# aHam_just_captm.net
KiCad netlist of a schematic drawn in EAGLE
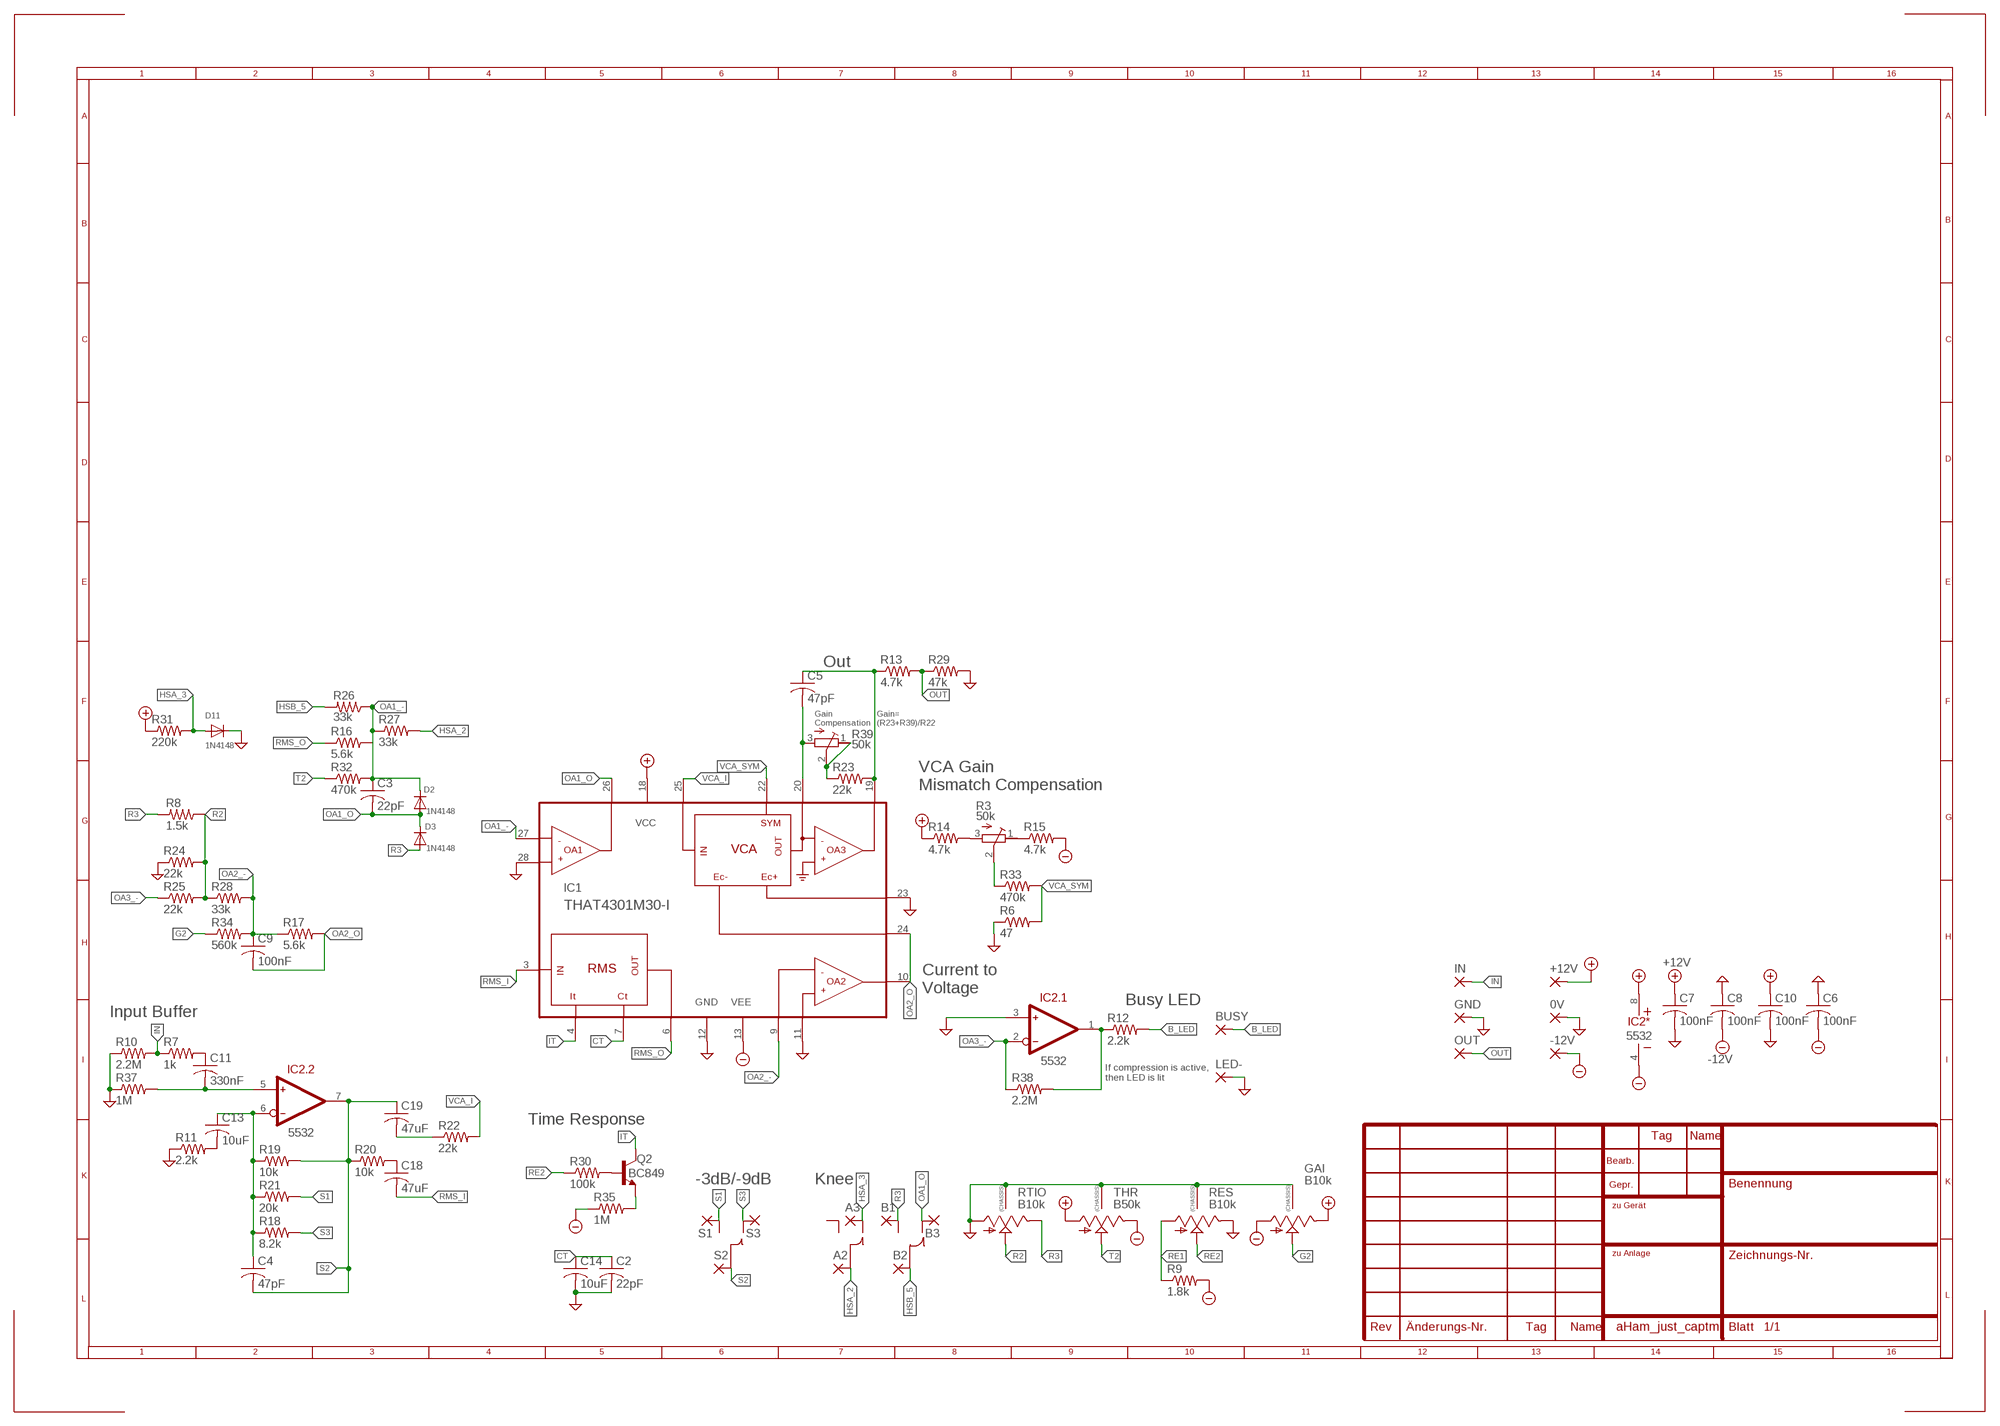
[diagram p0: schematic, sheet 1]

(export (version "E")
  (design (tool "Eeschema 10.0.6"))
  (components
    (comp (ref "+12V")
      (value "1,6/0,8")
      (footprint "eagle-import:1,6_0,8")
      (libsource (lib "eagle-import") (part "1,6/0,8"))
    )
    (comp (ref "-12V")
      (value "1,6/0,8")
      (footprint "eagle-import:1,6_0,8")
      (libsource (lib "eagle-import") (part "1,6/0,8"))
    )
    (comp (ref "0V")
      (value "1,6/0,8")
      (footprint "eagle-import:1,6_0,8")
      (libsource (lib "eagle-import") (part "1,6/0,8"))
    )
    (comp (ref "A2")
      (value "1,6/0,8")
      (footprint "eagle-import:1,6_0,8")
      (libsource (lib "eagle-import") (part "1,6/0,8"))
    )
    (comp (ref "A3")
      (value "1,6/0,8")
      (footprint "eagle-import:1,6_0,8")
      (libsource (lib "eagle-import") (part "1,6/0,8"))
    )
    (comp (ref "B1")
      (value "1,6/0,8")
      (footprint "eagle-import:1,6_0,8")
      (libsource (lib "eagle-import") (part "1,6/0,8"))
    )
    (comp (ref "B2")
      (value "1,6/0,8")
      (footprint "eagle-import:1,6_0,8")
      (libsource (lib "eagle-import") (part "1,6/0,8"))
    )
    (comp (ref "B3")
      (value "1,6/0,8")
      (footprint "eagle-import:1,6_0,8")
      (libsource (lib "eagle-import") (part "1,6/0,8"))
    )
    (comp (ref "BUSY")
      (value "1,6/0,8")
      (footprint "eagle-import:1,6_0,8")
      (libsource (lib "eagle-import") (part "1,6/0,8"))
    )
    (comp (ref "C2")
      (value "22pF")
      (footprint "eagle-import:C0805")
      (libsource (lib "eagle-import") (part "C-USC0805"))
    )
    (comp (ref "C3")
      (value "22pF")
      (footprint "eagle-import:C0805")
      (libsource (lib "eagle-import") (part "C-USC0805"))
    )
    (comp (ref "C4")
      (value "47pF")
      (footprint "eagle-import:C0805")
      (libsource (lib "eagle-import") (part "C-USC0805"))
    )
    (comp (ref "C5")
      (value "47pF")
      (footprint "eagle-import:C0805")
      (libsource (lib "eagle-import") (part "C-USC0805"))
    )
    (comp (ref "C6")
      (value "100nF")
      (footprint "eagle-import:C0805")
      (libsource (lib "eagle-import") (part "C-USC0805"))
    )
    (comp (ref "C7")
      (value "100nF")
      (footprint "eagle-import:C0805")
      (libsource (lib "eagle-import") (part "C-USC0805"))
    )
    (comp (ref "C8")
      (value "100nF")
      (footprint "eagle-import:C0805")
      (libsource (lib "eagle-import") (part "C-USC0805"))
    )
    (comp (ref "C9")
      (value "100nF")
      (footprint "eagle-import:C0805")
      (libsource (lib "eagle-import") (part "C-USC0805"))
    )
    (comp (ref "C10")
      (value "100nF")
      (footprint "eagle-import:C0805")
      (libsource (lib "eagle-import") (part "C-USC0805"))
    )
    (comp (ref "C11")
      (value "330nF")
      (footprint "eagle-import:C0805")
      (libsource (lib "eagle-import") (part "C-USC0805"))
    )
    (comp (ref "C13")
      (value "10uF")
      (footprint "eagle-import:C1206")
      (libsource (lib "eagle-import") (part "C-USC1206"))
    )
    (comp (ref "C14")
      (value "10uF")
      (footprint "eagle-import:C1206")
      (libsource (lib "eagle-import") (part "C-USC1206"))
    )
    (comp (ref "C18")
      (value "47uF")
      (footprint "eagle-import:C1206")
      (libsource (lib "eagle-import") (part "C-USC1206"))
    )
    (comp (ref "C19")
      (value "47uF")
      (footprint "eagle-import:C1206")
      (libsource (lib "eagle-import") (part "C-USC1206"))
    )
    (comp (ref "D2")
      (value "1N4148")
      (footprint "eagle-import:SOD-123")
      (libsource (lib "eagle-import") (part "DIODESOD-123"))
    )
    (comp (ref "D3")
      (value "1N4148")
      (footprint "eagle-import:SOD-123")
      (libsource (lib "eagle-import") (part "DIODESOD-123"))
    )
    (comp (ref "D11")
      (value "1N4148")
      (footprint "eagle-import:SOD-123")
      (libsource (lib "eagle-import") (part "DIODESOD-123"))
    )
    (comp (ref "GAI")
      (value "B10k")
      (footprint "eagle-import:9MM_SNAP-IN_POT")
      (libsource (lib "eagle-import") (part "9MM_SNAP-IN_POT_CHASSIS"))
    )
    (comp (ref "GND")
      (value "1,6/0,8")
      (footprint "eagle-import:1,6_0,8")
      (libsource (lib "eagle-import") (part "1,6/0,8"))
    )
    (comp (ref "IC1")
      (value "THAT4301M30-I")
      (footprint "eagle-import:SO30W")
      (libsource (lib "eagle-import") (part "THAT4301M30-I"))
    )
    (comp (ref "IC2")
      (value "5532")
      (footprint "eagle-import:SO-8")
      (libsource (lib "eagle-import") (part "NJM5532M"))
    )
    (comp (ref "IN")
      (value "1,6/0,8")
      (footprint "eagle-import:1,6_0,8")
      (libsource (lib "eagle-import") (part "1,6/0,8"))
    )
    (comp (ref "LED-")
      (value "1,6/0,8")
      (footprint "eagle-import:1,6_0,8")
      (libsource (lib "eagle-import") (part "1,6/0,8"))
    )
    (comp (ref "OUT")
      (value "1,6/0,8")
      (footprint "eagle-import:1,6_0,8")
      (libsource (lib "eagle-import") (part "1,6/0,8"))
    )
    (comp (ref "Q2")
      (value "BC849")
      (footprint "eagle-import:SOT23-BEC")
      (libsource (lib "eagle-import") (part "-NPN-SOT23-BECBC849"))
    )
    (comp (ref "R3")
      (value "50k")
      (footprint "eagle-import:RTRIM3314G")
      (libsource (lib "eagle-import") (part "R-TRIMM3314G"))
    )
    (comp (ref "R6")
      (value "47")
      (footprint "eagle-import:R0805")
      (libsource (lib "eagle-import") (part "R-US_R0805"))
    )
    (comp (ref "R7")
      (value "1k")
      (footprint "eagle-import:R0805")
      (libsource (lib "eagle-import") (part "R-US_R0805"))
    )
    (comp (ref "R8")
      (value "1.5k")
      (footprint "eagle-import:R0805")
      (libsource (lib "eagle-import") (part "R-US_R0805"))
    )
    (comp (ref "R9")
      (value "1.8k")
      (footprint "eagle-import:R0805")
      (libsource (lib "eagle-import") (part "R-US_R0805"))
    )
    (comp (ref "R10")
      (value "2.2M")
      (footprint "eagle-import:R0805")
      (libsource (lib "eagle-import") (part "R-US_R0805"))
    )
    (comp (ref "R11")
      (value "2.2k")
      (footprint "eagle-import:R0805")
      (libsource (lib "eagle-import") (part "R-US_R0805"))
    )
    (comp (ref "R12")
      (value "2.2k")
      (footprint "eagle-import:R0805")
      (libsource (lib "eagle-import") (part "R-US_R0805"))
    )
    (comp (ref "R13")
      (value "4.7k")
      (footprint "eagle-import:R0805")
      (libsource (lib "eagle-import") (part "R-US_R0805"))
    )
    (comp (ref "R14")
      (value "4.7k")
      (footprint "eagle-import:R0805")
      (libsource (lib "eagle-import") (part "R-US_R0805"))
    )
    (comp (ref "R15")
      (value "4.7k")
      (footprint "eagle-import:R0805")
      (libsource (lib "eagle-import") (part "R-US_R0805"))
    )
    (comp (ref "R16")
      (value "5.6k")
      (footprint "eagle-import:R0805")
      (libsource (lib "eagle-import") (part "R-US_R0805"))
    )
    (comp (ref "R17")
      (value "5.6k")
      (footprint "eagle-import:R0805")
      (libsource (lib "eagle-import") (part "R-US_R0805"))
    )
    (comp (ref "R18")
      (value "8.2k")
      (footprint "eagle-import:R0805")
      (libsource (lib "eagle-import") (part "R-US_R0805"))
    )
    (comp (ref "R19")
      (value "10k")
      (footprint "eagle-import:R0805")
      (libsource (lib "eagle-import") (part "R-US_R0805"))
    )
    (comp (ref "R20")
      (value "10k")
      (footprint "eagle-import:R0805")
      (libsource (lib "eagle-import") (part "R-US_R0805"))
    )
    (comp (ref "R21")
      (value "20k")
      (footprint "eagle-import:R0805")
      (libsource (lib "eagle-import") (part "R-US_R0805"))
    )
    (comp (ref "R22")
      (value "22k")
      (footprint "eagle-import:R0805")
      (libsource (lib "eagle-import") (part "R-US_R0805"))
    )
    (comp (ref "R23")
      (value "22k")
      (footprint "eagle-import:R0805")
      (libsource (lib "eagle-import") (part "R-US_R0805"))
    )
    (comp (ref "R24")
      (value "22k")
      (footprint "eagle-import:R0805")
      (libsource (lib "eagle-import") (part "R-US_R0805"))
    )
    (comp (ref "R25")
      (value "22k")
      (footprint "eagle-import:R0805")
      (libsource (lib "eagle-import") (part "R-US_R0805"))
    )
    (comp (ref "R26")
      (value "33k")
      (footprint "eagle-import:R0805")
      (libsource (lib "eagle-import") (part "R-US_R0805"))
    )
    (comp (ref "R27")
      (value "33k")
      (footprint "eagle-import:R0805")
      (libsource (lib "eagle-import") (part "R-US_R0805"))
    )
    (comp (ref "R28")
      (value "33k")
      (footprint "eagle-import:R0805")
      (libsource (lib "eagle-import") (part "R-US_R0805"))
    )
    (comp (ref "R29")
      (value "47k")
      (footprint "eagle-import:R0805")
      (libsource (lib "eagle-import") (part "R-US_R0805"))
    )
    (comp (ref "R30")
      (value "100k")
      (footprint "eagle-import:R0805")
      (libsource (lib "eagle-import") (part "R-US_R0805"))
    )
    (comp (ref "R31")
      (value "220k")
      (footprint "eagle-import:R0805")
      (libsource (lib "eagle-import") (part "R-US_R0805"))
    )
    (comp (ref "R32")
      (value "470k")
      (footprint "eagle-import:R0805")
      (libsource (lib "eagle-import") (part "R-US_R0805"))
    )
    (comp (ref "R33")
      (value "470k")
      (footprint "eagle-import:R0805")
      (libsource (lib "eagle-import") (part "R-US_R0805"))
    )
    (comp (ref "R34")
      (value "560k")
      (footprint "eagle-import:R0805")
      (libsource (lib "eagle-import") (part "R-US_R0805"))
    )
    (comp (ref "R35")
      (value "1M")
      (footprint "eagle-import:R0805")
      (libsource (lib "eagle-import") (part "R-US_R0805"))
    )
    (comp (ref "R37")
      (value "1M")
      (footprint "eagle-import:R0805")
      (libsource (lib "eagle-import") (part "R-US_R0805"))
    )
    (comp (ref "R38")
      (value "2.2M")
      (footprint "eagle-import:R0805")
      (libsource (lib "eagle-import") (part "R-US_R0805"))
    )
    (comp (ref "R39")
      (value "50k")
      (footprint "eagle-import:RTRIM3314G")
      (libsource (lib "eagle-import") (part "R-TRIMM3314G"))
    )
    (comp (ref "RES")
      (value "B10k")
      (footprint "eagle-import:9MM_SNAP-IN_POT")
      (libsource (lib "eagle-import") (part "9MM_SNAP-IN_POT_CHASSIS"))
    )
    (comp (ref "RTIO")
      (value "B10k")
      (footprint "eagle-import:9MM_SNAP-IN_POT")
      (libsource (lib "eagle-import") (part "9MM_SNAP-IN_POT_CHASSIS"))
    )
    (comp (ref "S1")
      (value "1,6/0,8")
      (footprint "eagle-import:1,6_0,8")
      (libsource (lib "eagle-import") (part "1,6/0,8"))
    )
    (comp (ref "S2")
      (value "1,6/0,8")
      (footprint "eagle-import:1,6_0,8")
      (libsource (lib "eagle-import") (part "1,6/0,8"))
    )
    (comp (ref "S3")
      (value "1,6/0,8")
      (footprint "eagle-import:1,6_0,8")
      (libsource (lib "eagle-import") (part "1,6/0,8"))
    )
    (comp (ref "THR")
      (value "B50k")
      (footprint "eagle-import:9MM_SNAP-IN_POT")
      (libsource (lib "eagle-import") (part "9MM_SNAP-IN_POT_CHASSIS"))
    )
  )
  (nets
    (net (code "1") (name "+12V") (class "Default")
      (node (ref "+12V") (pin "1") (pinfunction "P_1") (pintype "passive"))
      (node (ref "C10") (pin "1") (pinfunction "1_1") (pintype "passive"))
      (node (ref "C7") (pin "1") (pinfunction "1_1") (pintype "passive"))
      (node (ref "GAI") (pin "3") (pinfunction "E_3") (pintype "passive"))
      (node (ref "IC1") (pin "18") (pinfunction "VCC_18") (pintype "power_in"))
      (node (ref "IC2") (pin "8") (pinfunction "V+_8") (pintype "power_in"))
      (node (ref "R14") (pin "1") (pinfunction "1_1") (pintype "passive"))
      (node (ref "R31") (pin "1") (pinfunction "1_1") (pintype "passive"))
      (node (ref "THR") (pin "1") (pinfunction "A_1") (pintype "passive"))
    )
    (net (code "2") (name "-12V") (class "Default")
      (node (ref "-12V") (pin "1") (pinfunction "P_1") (pintype "passive"))
      (node (ref "C6") (pin "2") (pinfunction "2_2") (pintype "passive"))
      (node (ref "C8") (pin "2") (pinfunction "2_2") (pintype "passive"))
      (node (ref "GAI") (pin "1") (pinfunction "A_1") (pintype "passive"))
      (node (ref "IC1") (pin "13") (pinfunction "VEE_13") (pintype "power_in"))
      (node (ref "IC2") (pin "4") (pinfunction "V-_4") (pintype "power_in"))
      (node (ref "R15") (pin "2") (pinfunction "2_2") (pintype "passive"))
      (node (ref "R35") (pin "1") (pinfunction "1_1") (pintype "passive"))
      (node (ref "R9") (pin "2") (pinfunction "2_2") (pintype "passive"))
      (node (ref "THR") (pin "3") (pinfunction "E_3") (pintype "passive"))
    )
    (net (code "3") (name "B_LED") (class "Default")
      (node (ref "BUSY") (pin "1") (pinfunction "P_1") (pintype "passive"))
      (node (ref "R12") (pin "2") (pinfunction "2_2") (pintype "passive"))
    )
    (net (code "4") (name "CT") (class "Default")
      (node (ref "C14") (pin "1") (pinfunction "1_1") (pintype "passive"))
      (node (ref "C2") (pin "1") (pinfunction "1_1") (pintype "passive"))
      (node (ref "IC1") (pin "7") (pinfunction "CT_7") (pintype "passive"))
    )
    (net (code "5") (name "G2") (class "Default")
      (node (ref "GAI") (pin "2") (pinfunction "S_2") (pintype "passive"))
      (node (ref "R34") (pin "1") (pinfunction "1_1") (pintype "passive"))
    )
    (net (code "6") (name "GND") (class "Default")
      (node (ref "0V") (pin "1") (pinfunction "P_1") (pintype "passive"))
      (node (ref "C10") (pin "2") (pinfunction "2_2") (pintype "passive"))
      (node (ref "C14") (pin "2") (pinfunction "2_2") (pintype "passive"))
      (node (ref "C2") (pin "2") (pinfunction "2_2") (pintype "passive"))
      (node (ref "C6") (pin "1") (pinfunction "1_1") (pintype "passive"))
      (node (ref "C7") (pin "2") (pinfunction "2_2") (pintype "passive"))
      (node (ref "C8") (pin "1") (pinfunction "1_1") (pintype "passive"))
      (node (ref "D11") (pin "C") (pinfunction "C_C") (pintype "passive"))
      (node (ref "GAI") (pin "CHASSIS1") (pinfunction "P$1_CHASSIS1") (pintype "passive"))
      (node (ref "GAI") (pin "CHASSIS2") (pinfunction "P$1_CHASSIS2") (pintype "passive"))
      (node (ref "GND") (pin "1") (pinfunction "P_1") (pintype "passive"))
      (node (ref "IC1") (pin "11") (pinfunction "OA2_+IN_11") (pintype "bidirectional"))
      (node (ref "IC1") (pin "12") (pinfunction "GND_12") (pintype "power_in"))
      (node (ref "IC1") (pin "23") (pinfunction "EC+_23") (pintype "passive"))
      (node (ref "IC1") (pin "28") (pinfunction "OA1_+IN_28") (pintype "input"))
      (node (ref "IC2") (pin "3") (pinfunction "IN+_3") (pintype "input"))
      (node (ref "LED-") (pin "1") (pinfunction "P_1") (pintype "passive"))
      (node (ref "R10") (pin "1") (pinfunction "1_1") (pintype "passive"))
      (node (ref "R11") (pin "1") (pinfunction "1_1") (pintype "passive"))
      (node (ref "R24") (pin "1") (pinfunction "1_1") (pintype "passive"))
      (node (ref "R29") (pin "2") (pinfunction "2_2") (pintype "passive"))
      (node (ref "R37") (pin "1") (pinfunction "1_1") (pintype "passive"))
      (node (ref "R6") (pin "1") (pinfunction "1_1") (pintype "passive"))
      (node (ref "RES") (pin "3") (pinfunction "E_3") (pintype "passive"))
      (node (ref "RES") (pin "CHASSIS1") (pinfunction "P$1_CHASSIS1") (pintype "passive"))
      (node (ref "RES") (pin "CHASSIS2") (pinfunction "P$1_CHASSIS2") (pintype "passive"))
      (node (ref "RTIO") (pin "1") (pinfunction "A_1") (pintype "passive"))
      (node (ref "RTIO") (pin "CHASSIS1") (pinfunction "P$1_CHASSIS1") (pintype "passive"))
      (node (ref "RTIO") (pin "CHASSIS2") (pinfunction "P$1_CHASSIS2") (pintype "passive"))
      (node (ref "THR") (pin "CHASSIS1") (pinfunction "P$1_CHASSIS1") (pintype "passive"))
      (node (ref "THR") (pin "CHASSIS2") (pinfunction "P$1_CHASSIS2") (pintype "passive"))
    )
    (net (code "7") (name "HSA_2") (class "Default")
      (node (ref "A2") (pin "1") (pinfunction "P_1") (pintype "passive"))
      (node (ref "R27") (pin "2") (pinfunction "2_2") (pintype "passive"))
    )
    (net (code "8") (name "HSA_3") (class "Default")
      (node (ref "A3") (pin "1") (pinfunction "P_1") (pintype "passive"))
      (node (ref "D11") (pin "A") (pinfunction "A_A") (pintype "passive"))
      (node (ref "R31") (pin "2") (pinfunction "2_2") (pintype "passive"))
    )
    (net (code "9") (name "HSB_5") (class "Default")
      (node (ref "B2") (pin "1") (pinfunction "P_1") (pintype "passive"))
      (node (ref "R26") (pin "2") (pinfunction "2_2") (pintype "passive"))
    )
    (net (code "10") (name "IN") (class "Default")
      (node (ref "IN") (pin "1") (pinfunction "P_1") (pintype "passive"))
      (node (ref "R10") (pin "2") (pinfunction "2_2") (pintype "passive"))
      (node (ref "R7") (pin "1") (pinfunction "1_1") (pintype "passive"))
    )
    (net (code "11") (name "IT") (class "Default")
      (node (ref "IC1") (pin "4") (pinfunction "IT_4") (pintype "passive"))
      (node (ref "Q2") (pin "C") (pinfunction "C_C") (pintype "passive"))
    )
    (net (code "12") (name "Net-(C11-Pad1)") (class "Default")
      (node (ref "C11") (pin "1") (pinfunction "1_1") (pintype "passive"))
      (node (ref "R7") (pin "2") (pinfunction "2_2") (pintype "passive"))
    )
    (net (code "13") (name "Net-(C13-Pad2)") (class "Default")
      (node (ref "C13") (pin "2") (pinfunction "2_2") (pintype "passive"))
      (node (ref "R11") (pin "2") (pinfunction "2_2") (pintype "passive"))
    )
    (net (code "14") (name "Net-(C18-Pad1)") (class "Default")
      (node (ref "C18") (pin "1") (pinfunction "1_1") (pintype "passive"))
      (node (ref "R20") (pin "2") (pinfunction "2_2") (pintype "passive"))
    )
    (net (code "15") (name "Net-(C19-Pad2)") (class "Default")
      (node (ref "C19") (pin "2") (pinfunction "2_2") (pintype "passive"))
      (node (ref "R22") (pin "1") (pinfunction "1_1") (pintype "passive"))
    )
    (net (code "16") (name "Net-(IC1-OA3_OUT)") (class "Default")
      (node (ref "C5") (pin "1") (pinfunction "1_1") (pintype "passive"))
      (node (ref "IC1") (pin "19") (pinfunction "OA3_OUT_19") (pintype "output"))
      (node (ref "R13") (pin "1") (pinfunction "1_1") (pintype "passive"))
      (node (ref "R23") (pin "2") (pinfunction "2_2") (pintype "passive"))
    )
    (net (code "17") (name "Net-(IC1-VCA_OUT)") (class "Default")
      (node (ref "C5") (pin "2") (pinfunction "2_2") (pintype "passive"))
      (node (ref "IC1") (pin "20") (pinfunction "VCA_OUT_20") (pintype "passive"))
      (node (ref "R39") (pin "3") (pinfunction "A_3") (pintype "passive"))
    )
    (net (code "18") (name "Net-(IC2B-OUT)") (class "Default")
      (node (ref "IC2") (pin "1") (pinfunction "OUT_1") (pintype "output"))
      (node (ref "R12") (pin "1") (pinfunction "1_1") (pintype "passive"))
      (node (ref "R38") (pin "2") (pinfunction "2_2") (pintype "passive"))
    )
    (net (code "19") (name "Net-(IC2C-IN+)") (class "Default")
      (node (ref "C11") (pin "2") (pinfunction "2_2") (pintype "passive"))
      (node (ref "IC2") (pin "5") (pinfunction "IN+_5") (pintype "input"))
      (node (ref "R37") (pin "2") (pinfunction "2_2") (pintype "passive"))
    )
    (net (code "20") (name "Net-(IC2C-IN-)") (class "Default")
      (node (ref "C13") (pin "1") (pinfunction "1_1") (pintype "passive"))
      (node (ref "C4") (pin "1") (pinfunction "1_1") (pintype "passive"))
      (node (ref "IC2") (pin "6") (pinfunction "IN-_6") (pintype "input"))
      (node (ref "R18") (pin "1") (pinfunction "1_1") (pintype "passive"))
      (node (ref "R19") (pin "1") (pinfunction "1_1") (pintype "passive"))
      (node (ref "R21") (pin "1") (pinfunction "1_1") (pintype "passive"))
    )
    (net (code "21") (name "Net-(Q2-PadB)") (class "Default")
      (node (ref "Q2") (pin "B") (pinfunction "B_B") (pintype "passive"))
      (node (ref "R30") (pin "2") (pinfunction "2_2") (pintype "passive"))
    )
    (net (code "22") (name "Net-(Q2-PadE)") (class "Default")
      (node (ref "Q2") (pin "E") (pinfunction "E_E") (pintype "passive"))
      (node (ref "R35") (pin "2") (pinfunction "2_2") (pintype "passive"))
    )
    (net (code "23") (name "Net-(R3-A)") (class "Default")
      (node (ref "R14") (pin "2") (pinfunction "2_2") (pintype "passive"))
      (node (ref "R3") (pin "3") (pinfunction "A_3") (pintype "passive"))
    )
    (net (code "24") (name "Net-(R3-E)") (class "Default")
      (node (ref "R15") (pin "1") (pinfunction "1_1") (pintype "passive"))
      (node (ref "R3") (pin "1") (pinfunction "E_1") (pintype "passive"))
    )
    (net (code "25") (name "Net-(R3-S)") (class "Default")
      (node (ref "R3") (pin "2") (pinfunction "S_2") (pintype "passive"))
      (node (ref "R33") (pin "1") (pinfunction "1_1") (pintype "passive"))
    )
    (net (code "26") (name "Net-(R39-E)") (class "Default")
      (node (ref "R23") (pin "1") (pinfunction "1_1") (pintype "passive"))
      (node (ref "R39") (pin "1") (pinfunction "E_1") (pintype "passive"))
      (node (ref "R39") (pin "2") (pinfunction "S_2") (pintype "passive"))
    )
    (net (code "27") (name "OA1_-") (class "Default")
      (node (ref "C3") (pin "1") (pinfunction "1_1") (pintype "passive"))
      (node (ref "D2") (pin "C") (pinfunction "C_C") (pintype "passive"))
      (node (ref "IC1") (pin "27") (pinfunction "OA1_-IN_27") (pintype "input"))
      (node (ref "R16") (pin "2") (pinfunction "2_2") (pintype "passive"))
      (node (ref "R26") (pin "1") (pinfunction "1_1") (pintype "passive"))
      (node (ref "R27") (pin "1") (pinfunction "1_1") (pintype "passive"))
      (node (ref "R32") (pin "2") (pinfunction "2_2") (pintype "passive"))
    )
    (net (code "28") (name "OA1_O") (class "Default")
      (node (ref "B3") (pin "1") (pinfunction "P_1") (pintype "passive"))
      (node (ref "C3") (pin "2") (pinfunction "2_2") (pintype "passive"))
      (node (ref "D2") (pin "A") (pinfunction "A_A") (pintype "passive"))
      (node (ref "D3") (pin "C") (pinfunction "C_C") (pintype "passive"))
      (node (ref "IC1") (pin "26") (pinfunction "OA1_OUT_26") (pintype "output"))
    )
    (net (code "29") (name "OA2_-") (class "Default")
      (node (ref "C9") (pin "1") (pinfunction "1_1") (pintype "passive"))
      (node (ref "IC1") (pin "9") (pinfunction "OA2_-IN_9") (pintype "bidirectional"))
      (node (ref "R17") (pin "1") (pinfunction "1_1") (pintype "passive"))
      (node (ref "R28") (pin "2") (pinfunction "2_2") (pintype "passive"))
      (node (ref "R34") (pin "2") (pinfunction "2_2") (pintype "passive"))
    )
    (net (code "30") (name "OA2_O") (class "Default")
      (node (ref "C9") (pin "2") (pinfunction "2_2") (pintype "passive"))
      (node (ref "IC1") (pin "10") (pinfunction "OA2_OUT_10") (pintype "output"))
      (node (ref "IC1") (pin "24") (pinfunction "EC-_24") (pintype "passive"))
      (node (ref "R17") (pin "2") (pinfunction "2_2") (pintype "passive"))
    )
    (net (code "31") (name "OA3_-") (class "Default")
      (node (ref "IC2") (pin "2") (pinfunction "IN-_2") (pintype "input"))
      (node (ref "R25") (pin "1") (pinfunction "1_1") (pintype "passive"))
      (node (ref "R38") (pin "1") (pinfunction "1_1") (pintype "passive"))
    )
    (net (code "32") (name "OUT") (class "Default")
      (node (ref "OUT") (pin "1") (pinfunction "P_1") (pintype "passive"))
      (node (ref "R13") (pin "2") (pinfunction "2_2") (pintype "passive"))
      (node (ref "R29") (pin "1") (pinfunction "1_1") (pintype "passive"))
    )
    (net (code "33") (name "R2") (class "Default")
      (node (ref "R24") (pin "2") (pinfunction "2_2") (pintype "passive"))
      (node (ref "R25") (pin "2") (pinfunction "2_2") (pintype "passive"))
      (node (ref "R28") (pin "1") (pinfunction "1_1") (pintype "passive"))
      (node (ref "R8") (pin "1") (pinfunction "1_1") (pintype "passive"))
      (node (ref "RTIO") (pin "2") (pinfunction "S_2") (pintype "passive"))
    )
    (net (code "34") (name "R3") (class "Default")
      (node (ref "B1") (pin "1") (pinfunction "P_1") (pintype "passive"))
      (node (ref "D3") (pin "A") (pinfunction "A_A") (pintype "passive"))
      (node (ref "R8") (pin "2") (pinfunction "2_2") (pintype "passive"))
      (node (ref "RTIO") (pin "3") (pinfunction "E_3") (pintype "passive"))
    )
    (net (code "35") (name "RE1") (class "Default")
      (node (ref "R9") (pin "1") (pinfunction "1_1") (pintype "passive"))
      (node (ref "RES") (pin "1") (pinfunction "A_1") (pintype "passive"))
    )
    (net (code "36") (name "RE2") (class "Default")
      (node (ref "R30") (pin "1") (pinfunction "1_1") (pintype "passive"))
      (node (ref "RES") (pin "2") (pinfunction "S_2") (pintype "passive"))
    )
    (net (code "37") (name "RMS_I") (class "Default")
      (node (ref "C18") (pin "2") (pinfunction "2_2") (pintype "passive"))
      (node (ref "IC1") (pin "3") (pinfunction "RMS_IN_3") (pintype "input"))
    )
    (net (code "38") (name "RMS_O") (class "Default")
      (node (ref "IC1") (pin "6") (pinfunction "RMS_OUT_6") (pintype "output"))
      (node (ref "R16") (pin "1") (pinfunction "1_1") (pintype "passive"))
    )
    (net (code "39") (name "S1") (class "Default")
      (node (ref "R21") (pin "2") (pinfunction "2_2") (pintype "passive"))
      (node (ref "S1") (pin "1") (pinfunction "P_1") (pintype "passive"))
    )
    (net (code "40") (name "S2") (class "Default")
      (node (ref "C19") (pin "1") (pinfunction "1_1") (pintype "passive"))
      (node (ref "C4") (pin "2") (pinfunction "2_2") (pintype "passive"))
      (node (ref "IC2") (pin "7") (pinfunction "OUT_7") (pintype "output"))
      (node (ref "R19") (pin "2") (pinfunction "2_2") (pintype "passive"))
      (node (ref "R20") (pin "1") (pinfunction "1_1") (pintype "passive"))
      (node (ref "S2") (pin "1") (pinfunction "P_1") (pintype "passive"))
    )
    (net (code "41") (name "S3") (class "Default")
      (node (ref "R18") (pin "2") (pinfunction "2_2") (pintype "passive"))
      (node (ref "S3") (pin "1") (pinfunction "P_1") (pintype "passive"))
    )
    (net (code "42") (name "T2") (class "Default")
      (node (ref "R32") (pin "1") (pinfunction "1_1") (pintype "passive"))
      (node (ref "THR") (pin "2") (pinfunction "S_2") (pintype "passive"))
    )
    (net (code "43") (name "VCA_I") (class "Default")
      (node (ref "IC1") (pin "25") (pinfunction "VCA_IN_25") (pintype "input"))
      (node (ref "R22") (pin "2") (pinfunction "2_2") (pintype "passive"))
    )
    (net (code "44") (name "VCA_SYM") (class "Default")
      (node (ref "IC1") (pin "22") (pinfunction "SYM_22") (pintype "passive"))
      (node (ref "R33") (pin "2") (pinfunction "2_2") (pintype "passive"))
      (node (ref "R6") (pin "2") (pinfunction "2_2") (pintype "passive"))
    )
  )
)
